# recorder.net
KiCad netlist of a schematic drawn in EAGLE
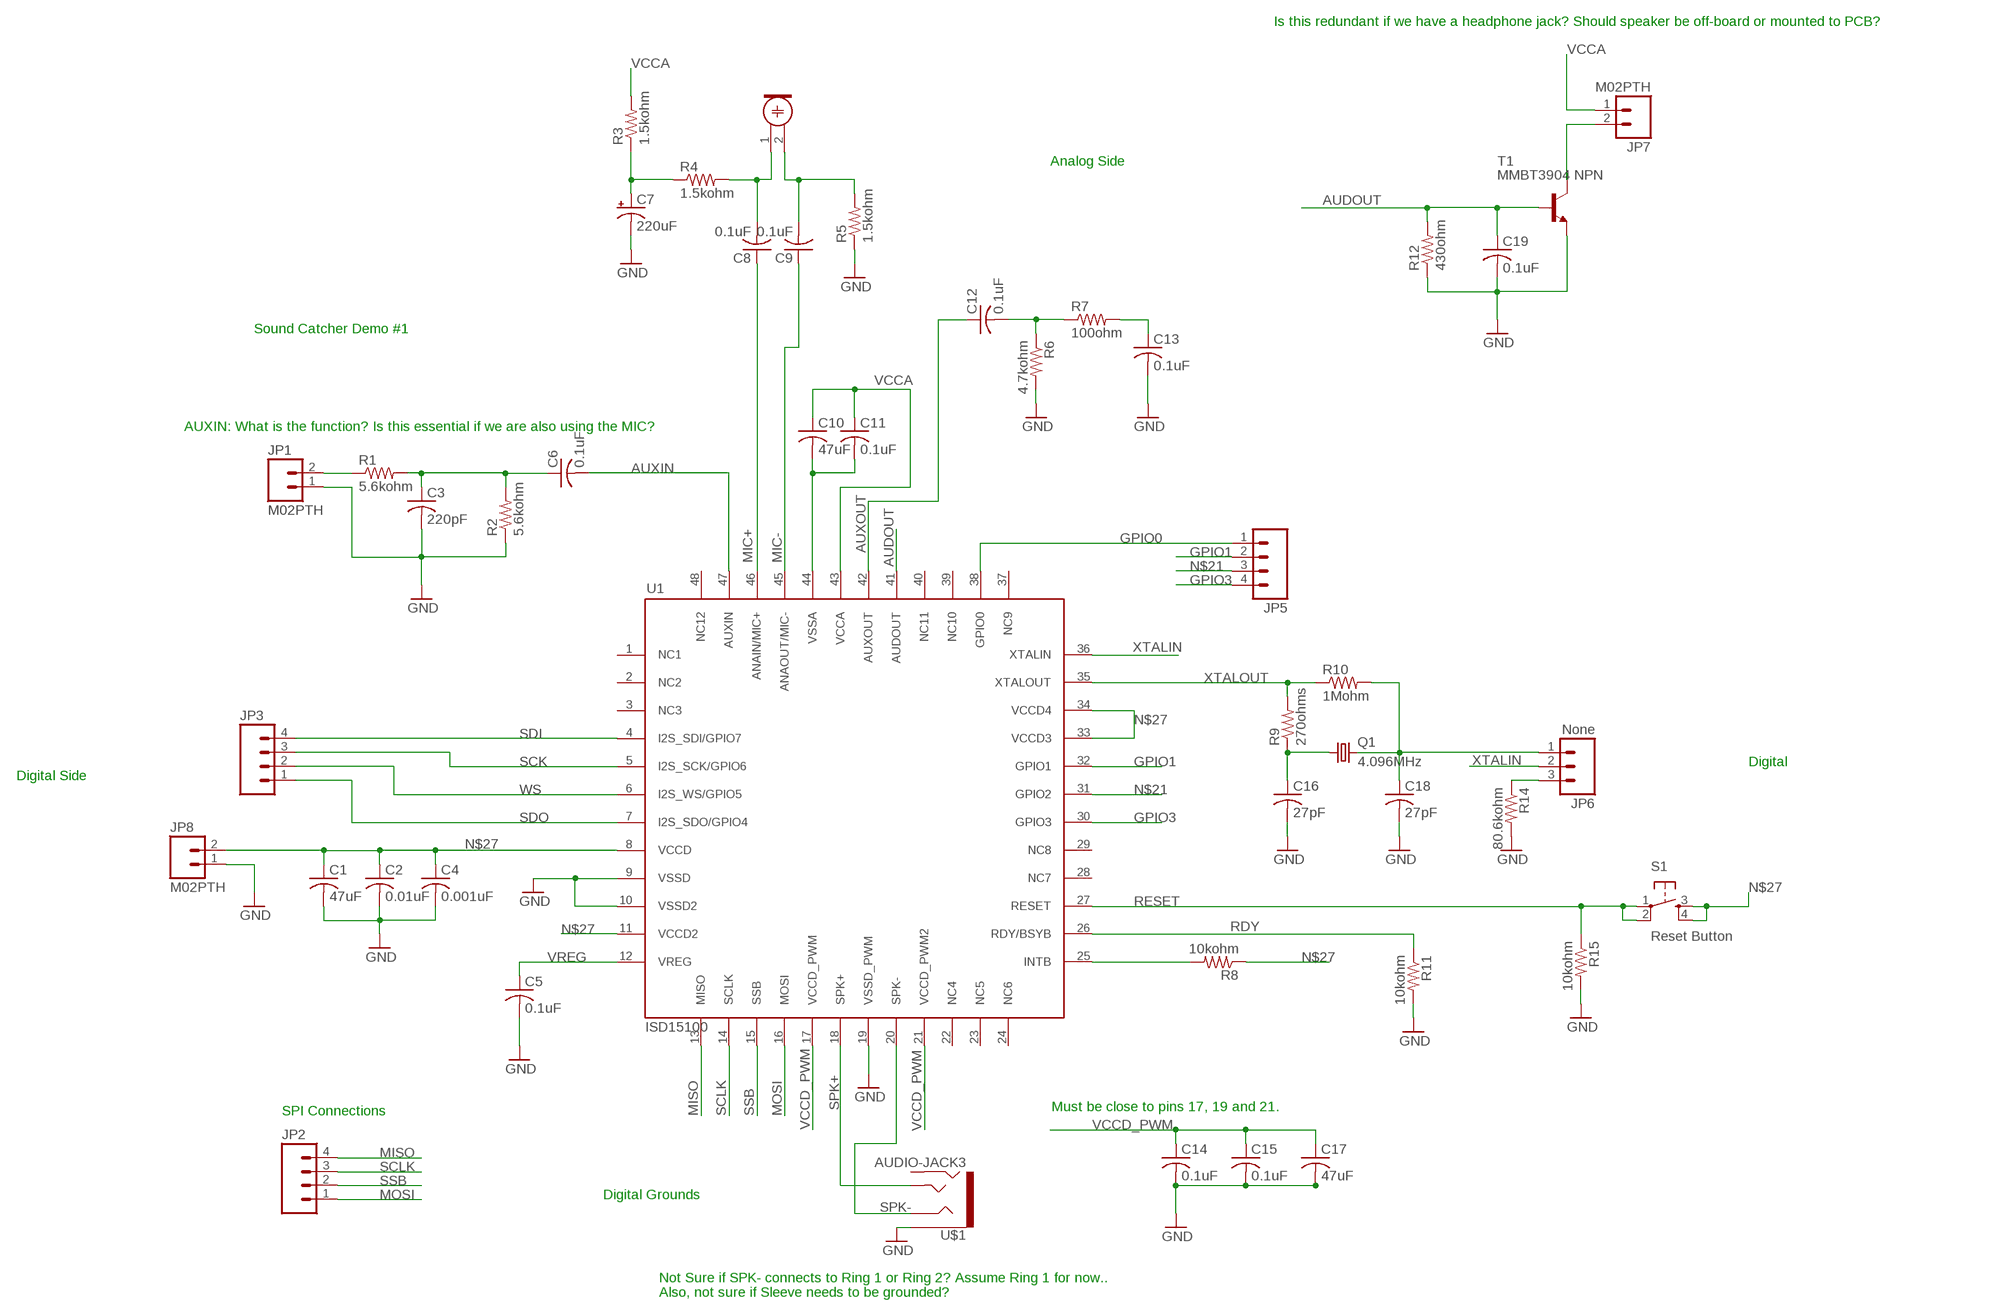
[diagram p0: schematic, sheet 1]

(export (version "E")
  (design (tool "Eeschema 10.0.6"))
  (components
    (comp (ref "C1")
      (value "47uF")
      (footprint "eagle-import:C1206")
      (libsource (lib "eagle-import") (part "C-USC1206"))
    )
    (comp (ref "C2")
      (value "0.01uF")
      (footprint "eagle-import:C0402")
      (libsource (lib "eagle-import") (part "C-USC0402"))
    )
    (comp (ref "C3")
      (value "220pF")
      (footprint "eagle-import:C0402")
      (libsource (lib "eagle-import") (part "C-USC0402"))
    )
    (comp (ref "C4")
      (value "0.001uF")
      (footprint "eagle-import:C0402")
      (libsource (lib "eagle-import") (part "C-USC0402"))
    )
    (comp (ref "C5")
      (value "0.1uF")
      (footprint "eagle-import:C0402")
      (libsource (lib "eagle-import") (part "C-USC0402"))
    )
    (comp (ref "C6")
      (value "0.1uF")
      (footprint "eagle-import:C0603")
      (libsource (lib "eagle-import") (part "C-USC0603"))
    )
    (comp (ref "C7")
      (value "220uF")
      (footprint "eagle-import:175TMP-0808")
      (libsource (lib "eagle-import") (part "CPOL-US175TMP-0808"))
    )
    (comp (ref "C8")
      (value "0.1uF")
      (footprint "eagle-import:C0402")
      (libsource (lib "eagle-import") (part "C-USC0402"))
    )
    (comp (ref "C9")
      (value "0.1uF")
      (footprint "eagle-import:C0402")
      (libsource (lib "eagle-import") (part "C-USC0402"))
    )
    (comp (ref "C10")
      (value "47uF")
      (footprint "eagle-import:C1206")
      (libsource (lib "eagle-import") (part "C-USC1206"))
    )
    (comp (ref "C11")
      (value "0.1uF")
      (footprint "eagle-import:C0402")
      (libsource (lib "eagle-import") (part "C-USC0402"))
    )
    (comp (ref "C12")
      (value "0.1uF")
      (footprint "eagle-import:C0402")
      (libsource (lib "eagle-import") (part "C-USC0402"))
    )
    (comp (ref "C13")
      (value "0.1uF")
      (footprint "eagle-import:C0402")
      (libsource (lib "eagle-import") (part "C-USC0402"))
    )
    (comp (ref "C14")
      (value "0.1uF")
      (footprint "eagle-import:C0402")
      (libsource (lib "eagle-import") (part "C-USC0402"))
    )
    (comp (ref "C15")
      (value "0.1uF")
      (footprint "eagle-import:C0402")
      (libsource (lib "eagle-import") (part "C-USC0402"))
    )
    (comp (ref "C16")
      (value "27pF")
      (footprint "eagle-import:C0402")
      (libsource (lib "eagle-import") (part "C-USC0402"))
    )
    (comp (ref "C17")
      (value "47uF")
      (footprint "eagle-import:C1206")
      (libsource (lib "eagle-import") (part "C-USC1206"))
    )
    (comp (ref "C18")
      (value "27pF")
      (footprint "eagle-import:C0402")
      (libsource (lib "eagle-import") (part "C-USC0402"))
    )
    (comp (ref "C19")
      (value "0.1uF")
      (footprint "eagle-import:C0402")
      (libsource (lib "eagle-import") (part "C-USC0402"))
    )
    (comp (ref "JP1")
      (value "M02PTH")
      (footprint "eagle-import:1X02")
      (libsource (lib "eagle-import") (part "M02PTH"))
    )
    (comp (ref "JP2")
      (value "M04PTH")
      (footprint "eagle-import:1X04")
      (libsource (lib "eagle-import") (part "M04PTH"))
    )
    (comp (ref "JP3")
      (value "M04PTH")
      (footprint "eagle-import:1X04")
      (libsource (lib "eagle-import") (part "M04PTH"))
    )
    (comp (ref "JP5")
      (value "M04PTH")
      (footprint "eagle-import:1X04")
      (libsource (lib "eagle-import") (part "M04PTH"))
    )
    (comp (ref "JP6")
      (value "None")
      (footprint "eagle-import:1X03")
      (libsource (lib "eagle-import") (part "M03PTH"))
    )
    (comp (ref "JP7")
      (value "M02PTH")
      (footprint "eagle-import:1X02")
      (libsource (lib "eagle-import") (part "M02PTH"))
    )
    (comp (ref "JP8")
      (value "M02PTH")
      (footprint "eagle-import:1X02")
      (libsource (lib "eagle-import") (part "M02PTH"))
    )
    (comp (ref "M1")
      (value "ELECTRET_MICROPHON-WM-61A")
      (footprint "eagle-import:WM-61A")
      (libsource (lib "eagle-import") (part "ELECTRET_MICROPHON-WM-61A"))
    )
    (comp (ref "Q1")
      (value "4.096MHz")
      (footprint "eagle-import:SM49")
      (libsource (lib "eagle-import") (part "CRYSTALSM49"))
    )
    (comp (ref "R1")
      (value "5.6kohm")
      (footprint "eagle-import:R0402")
      (libsource (lib "eagle-import") (part "R-US_R0402"))
    )
    (comp (ref "R2")
      (value "5.6kohm")
      (footprint "eagle-import:R0402")
      (libsource (lib "eagle-import") (part "R-US_R0402"))
    )
    (comp (ref "R3")
      (value "1.5kohm")
      (footprint "eagle-import:R0201")
      (fields (field (name "MF") "AVX CORPORATION") (field (name "MPN") "0402ZD104KAT2A"))
      (libsource (lib "eagle-import") (part "R-US_R0201"))
    )
    (comp (ref "R4")
      (value "1.5kohm")
      (footprint "eagle-import:R0201")
      (fields (field (name "MF") "AVX CORPORATION") (field (name "MPN") "0402ZD104KAT2A"))
      (libsource (lib "eagle-import") (part "R-US_R0201"))
    )
    (comp (ref "R5")
      (value "1.5kohm")
      (footprint "eagle-import:R0201")
      (fields (field (name "MF") "AVX CORPORATION") (field (name "MPN") "0402ZD104KAT2A"))
      (libsource (lib "eagle-import") (part "R-US_R0201"))
    )
    (comp (ref "R6")
      (value "4.7kohm")
      (footprint "eagle-import:R0201")
      (fields (field (name "MF") "AVX CORPORATION") (field (name "MPN") "0402ZD104KAT2A"))
      (libsource (lib "eagle-import") (part "R-US_R0201"))
    )
    (comp (ref "R7")
      (value "100ohm")
      (footprint "eagle-import:R0201")
      (fields (field (name "MF") "AVX CORPORATION") (field (name "MPN") "0402ZD104KAT2A"))
      (libsource (lib "eagle-import") (part "R-US_R0201"))
    )
    (comp (ref "R8")
      (value "10kohm")
      (footprint "eagle-import:R0201")
      (fields (field (name "MF") "AVX CORPORATION") (field (name "MPN") "0402ZD104KAT2A"))
      (libsource (lib "eagle-import") (part "R-US_R0201"))
    )
    (comp (ref "R9")
      (value "270ohms")
      (footprint "eagle-import:R0201")
      (fields (field (name "MF") "AVX CORPORATION") (field (name "MPN") "0402ZD104KAT2A"))
      (libsource (lib "eagle-import") (part "R-US_R0201"))
    )
    (comp (ref "R10")
      (value "1Mohm")
      (footprint "eagle-import:R0201")
      (fields (field (name "MF") "AVX CORPORATION") (field (name "MPN") "0402ZD104KAT2A"))
      (libsource (lib "eagle-import") (part "R-US_R0201"))
    )
    (comp (ref "R11")
      (value "10kohm")
      (footprint "eagle-import:R0201")
      (fields (field (name "MF") "AVX CORPORATION") (field (name "MPN") "0402ZD104KAT2A"))
      (libsource (lib "eagle-import") (part "R-US_R0201"))
    )
    (comp (ref "R12")
      (value "430ohm")
      (footprint "eagle-import:R0402")
      (libsource (lib "eagle-import") (part "R-US_R0402"))
    )
    (comp (ref "R14")
      (value "80.6kohm")
      (footprint "eagle-import:R0402")
      (libsource (lib "eagle-import") (part "R-US_R0402"))
    )
    (comp (ref "R15")
      (value "10kohm")
      (footprint "eagle-import:R0201")
      (fields (field (name "MF") "AVX CORPORATION") (field (name "MPN") "0402ZD104KAT2A"))
      (libsource (lib "eagle-import") (part "R-US_R0201"))
    )
    (comp (ref "S1")
      (value "Reset Button")
      (footprint "eagle-import:TACTILE-SWITCH-SMD")
      (libsource (lib "eagle-import") (part "TAC_SWITCHSMD"))
    )
    (comp (ref "T1")
      (value "MMBT3904 NPN")
      (footprint "eagle-import:SOT23-BEC")
      (libsource (lib "eagle-import") (part "-NPN-SOT23-BECMMBT3904LT1"))
    )
    (comp (ref "U$1")
      (value "AUDIO-JACK3")
      (footprint "eagle-import:AUDIO-JACK-TRRS-SMD")
      (libsource (lib "eagle-import") (part "AUDIO-JACK3"))
    )
    (comp (ref "U1")
      (value "ISD15100")
      (footprint "eagle-import:LQFP48")
      (libsource (lib "eagle-import") (part "ISD15100"))
    )
  )
  (nets
    (net (code "1") (name "/AUDOUT") (class "Default")
      (node (ref "C19") (pin "1") (pinfunction "1_1") (pintype "passive"))
      (node (ref "R12") (pin "2") (pinfunction "2_2") (pintype "passive"))
      (node (ref "T1") (pin "B") (pinfunction "B_B") (pintype "passive"))
      (node (ref "U1") (pin "41") (pinfunction "AUDOUT_41") (pintype "bidirectional"))
    )
    (net (code "2") (name "/AUXIN") (class "Default")
      (node (ref "C6") (pin "2") (pinfunction "2_2") (pintype "passive"))
      (node (ref "U1") (pin "47") (pinfunction "AUXIN_47") (pintype "bidirectional"))
    )
    (net (code "3") (name "/AUXOUT") (class "Default")
      (node (ref "C12") (pin "1") (pinfunction "1_1") (pintype "passive"))
      (node (ref "U1") (pin "42") (pinfunction "AUXOUT_42") (pintype "bidirectional"))
    )
    (net (code "4") (name "/GPIO0") (class "Default")
      (node (ref "JP5") (pin "1") (pinfunction "1_1") (pintype "passive"))
      (node (ref "U1") (pin "38") (pinfunction "GPIO0_38") (pintype "bidirectional"))
    )
    (net (code "5") (name "/GPIO1") (class "Default")
      (node (ref "JP5") (pin "2") (pinfunction "2_2") (pintype "passive"))
      (node (ref "U1") (pin "32") (pinfunction "GPIO1_32") (pintype "bidirectional"))
    )
    (net (code "6") (name "/GPIO3") (class "Default")
      (node (ref "JP5") (pin "4") (pinfunction "4_4") (pintype "passive"))
      (node (ref "U1") (pin "30") (pinfunction "GPIO3_30") (pintype "bidirectional"))
    )
    (net (code "7") (name "/MIC+") (class "Default")
      (node (ref "C8") (pin "1") (pinfunction "1_1") (pintype "passive"))
      (node (ref "U1") (pin "46") (pinfunction "ANAIN/MIC+_46") (pintype "bidirectional"))
    )
    (net (code "8") (name "/MIC-") (class "Default")
      (node (ref "C9") (pin "1") (pinfunction "1_1") (pintype "passive"))
      (node (ref "U1") (pin "45") (pinfunction "ANAOUT/MIC-_45") (pintype "bidirectional"))
    )
    (net (code "9") (name "/MISO") (class "Default")
      (node (ref "JP2") (pin "4") (pinfunction "4_4") (pintype "passive"))
      (node (ref "U1") (pin "13") (pinfunction "MISO_13") (pintype "bidirectional"))
    )
    (net (code "10") (name "/MOSI") (class "Default")
      (node (ref "JP2") (pin "1") (pinfunction "1_1") (pintype "passive"))
      (node (ref "U1") (pin "16") (pinfunction "MOSI_16") (pintype "bidirectional"))
    )
    (net (code "11") (name "/N$21") (class "Default")
      (node (ref "JP5") (pin "3") (pinfunction "3_3") (pintype "passive"))
      (node (ref "U1") (pin "31") (pinfunction "GPIO2_31") (pintype "bidirectional"))
    )
    (net (code "12") (name "/N$27") (class "Default")
      (node (ref "C1") (pin "1") (pinfunction "1_1") (pintype "passive"))
      (node (ref "C2") (pin "1") (pinfunction "1_1") (pintype "passive"))
      (node (ref "C4") (pin "1") (pinfunction "1_1") (pintype "passive"))
      (node (ref "JP8") (pin "2") (pinfunction "2_2") (pintype "passive"))
      (node (ref "R8") (pin "1") (pinfunction "1_1") (pintype "passive"))
      (node (ref "S1") (pin "3") (pinfunction "3_3") (pintype "passive"))
      (node (ref "S1") (pin "4") (pinfunction "4_4") (pintype "passive"))
      (node (ref "U1") (pin "11") (pinfunction "VCCD2_11") (pintype "bidirectional"))
      (node (ref "U1") (pin "33") (pinfunction "VCCD3_33") (pintype "bidirectional"))
      (node (ref "U1") (pin "34") (pinfunction "VCCD4_34") (pintype "bidirectional"))
      (node (ref "U1") (pin "8") (pinfunction "VCCD_8") (pintype "bidirectional"))
    )
    (net (code "13") (name "/RDY") (class "Default")
      (node (ref "R11") (pin "1") (pinfunction "1_1") (pintype "passive"))
      (node (ref "U1") (pin "26") (pinfunction "RDY/BSYB_26") (pintype "bidirectional"))
    )
    (net (code "14") (name "/RESET") (class "Default")
      (node (ref "R15") (pin "1") (pinfunction "1_1") (pintype "passive"))
      (node (ref "S1") (pin "1") (pinfunction "1_1") (pintype "passive"))
      (node (ref "S1") (pin "2") (pinfunction "2_2") (pintype "passive"))
      (node (ref "U1") (pin "27") (pinfunction "RESET_27") (pintype "bidirectional"))
    )
    (net (code "15") (name "/SCK") (class "Default")
      (node (ref "JP3") (pin "3") (pinfunction "3_3") (pintype "passive"))
      (node (ref "U1") (pin "5") (pinfunction "I2S_SCK/GPIO6_5") (pintype "bidirectional"))
    )
    (net (code "16") (name "/SCLK") (class "Default")
      (node (ref "JP2") (pin "3") (pinfunction "3_3") (pintype "passive"))
      (node (ref "U1") (pin "14") (pinfunction "SCLK_14") (pintype "bidirectional"))
    )
    (net (code "17") (name "/SDI") (class "Default")
      (node (ref "JP3") (pin "4") (pinfunction "4_4") (pintype "passive"))
      (node (ref "U1") (pin "4") (pinfunction "I2S_SDI/GPIO7_4") (pintype "bidirectional"))
    )
    (net (code "18") (name "/SDO") (class "Default")
      (node (ref "JP3") (pin "1") (pinfunction "1_1") (pintype "passive"))
      (node (ref "U1") (pin "7") (pinfunction "I2S_SDO/GPIO4_7") (pintype "bidirectional"))
    )
    (net (code "19") (name "/SPK+") (class "Default")
      (node (ref "U$1") (pin "TIP") (pinfunction "TIP_TIP") (pintype "bidirectional"))
      (node (ref "U1") (pin "18") (pinfunction "SPK+_18") (pintype "bidirectional"))
    )
    (net (code "20") (name "/SPK-") (class "Default")
      (node (ref "U$1") (pin "RING1") (pinfunction "RING1_RING1") (pintype "bidirectional"))
      (node (ref "U1") (pin "20") (pinfunction "SPK-_20") (pintype "bidirectional"))
    )
    (net (code "21") (name "/SSB") (class "Default")
      (node (ref "JP2") (pin "2") (pinfunction "2_2") (pintype "passive"))
      (node (ref "U1") (pin "15") (pinfunction "SSB_15") (pintype "bidirectional"))
    )
    (net (code "22") (name "/VCCA") (class "Default")
      (node (ref "C10") (pin "1") (pinfunction "1_1") (pintype "passive"))
      (node (ref "C11") (pin "1") (pinfunction "1_1") (pintype "passive"))
      (node (ref "JP7") (pin "1") (pinfunction "1_1") (pintype "passive"))
      (node (ref "R3") (pin "2") (pinfunction "2_2") (pintype "passive"))
      (node (ref "U1") (pin "43") (pinfunction "VCCA_43") (pintype "bidirectional"))
    )
    (net (code "23") (name "/VCCD_PWM") (class "Default")
      (node (ref "C14") (pin "1") (pinfunction "1_1") (pintype "passive"))
      (node (ref "C15") (pin "1") (pinfunction "1_1") (pintype "passive"))
      (node (ref "C17") (pin "1") (pinfunction "1_1") (pintype "passive"))
      (node (ref "U1") (pin "17") (pinfunction "VCCD_PWM_17") (pintype "bidirectional"))
      (node (ref "U1") (pin "21") (pinfunction "VCCD_PWM2_21") (pintype "bidirectional"))
    )
    (net (code "24") (name "/VREG") (class "Default")
      (node (ref "C5") (pin "1") (pinfunction "1_1") (pintype "passive"))
      (node (ref "U1") (pin "12") (pinfunction "VREG_12") (pintype "bidirectional"))
    )
    (net (code "25") (name "/WS") (class "Default")
      (node (ref "JP3") (pin "2") (pinfunction "2_2") (pintype "passive"))
      (node (ref "U1") (pin "6") (pinfunction "I2S_WS/GPIO5_6") (pintype "bidirectional"))
    )
    (net (code "26") (name "/XTALIN") (class "Default")
      (node (ref "JP6") (pin "2") (pinfunction "2_2") (pintype "passive"))
      (node (ref "U1") (pin "36") (pinfunction "XTALIN_36") (pintype "bidirectional"))
    )
    (net (code "27") (name "/XTALOUT") (class "Default")
      (node (ref "R10") (pin "1") (pinfunction "1_1") (pintype "passive"))
      (node (ref "R9") (pin "2") (pinfunction "2_2") (pintype "passive"))
      (node (ref "U1") (pin "35") (pinfunction "XTALOUT_35") (pintype "bidirectional"))
    )
    (net (code "28") (name "GND") (class "Default")
      (node (ref "C1") (pin "2") (pinfunction "2_2") (pintype "passive"))
      (node (ref "C13") (pin "2") (pinfunction "2_2") (pintype "passive"))
      (node (ref "C14") (pin "2") (pinfunction "2_2") (pintype "passive"))
      (node (ref "C15") (pin "2") (pinfunction "2_2") (pintype "passive"))
      (node (ref "C16") (pin "2") (pinfunction "2_2") (pintype "passive"))
      (node (ref "C17") (pin "2") (pinfunction "2_2") (pintype "passive"))
      (node (ref "C18") (pin "2") (pinfunction "2_2") (pintype "passive"))
      (node (ref "C19") (pin "2") (pinfunction "2_2") (pintype "passive"))
      (node (ref "C2") (pin "2") (pinfunction "2_2") (pintype "passive"))
      (node (ref "C3") (pin "2") (pinfunction "2_2") (pintype "passive"))
      (node (ref "C4") (pin "2") (pinfunction "2_2") (pintype "passive"))
      (node (ref "C5") (pin "2") (pinfunction "2_2") (pintype "passive"))
      (node (ref "C7") (pin "-") (pinfunction "-_-") (pintype "passive"))
      (node (ref "JP1") (pin "1") (pinfunction "1_1") (pintype "passive"))
      (node (ref "JP8") (pin "1") (pinfunction "1_1") (pintype "passive"))
      (node (ref "R11") (pin "2") (pinfunction "2_2") (pintype "passive"))
      (node (ref "R12") (pin "1") (pinfunction "1_1") (pintype "passive"))
      (node (ref "R14") (pin "2") (pinfunction "2_2") (pintype "passive"))
      (node (ref "R15") (pin "2") (pinfunction "2_2") (pintype "passive"))
      (node (ref "R2") (pin "1") (pinfunction "1_1") (pintype "passive"))
      (node (ref "R5") (pin "1") (pinfunction "1_1") (pintype "passive"))
      (node (ref "R6") (pin "2") (pinfunction "2_2") (pintype "passive"))
      (node (ref "T1") (pin "E") (pinfunction "E_E") (pintype "passive"))
      (node (ref "U$1") (pin "EARTH") (pinfunction "EARTH_EARTH") (pintype "bidirectional"))
      (node (ref "U1") (pin "10") (pinfunction "VSSD2_10") (pintype "bidirectional"))
      (node (ref "U1") (pin "19") (pinfunction "VSSD_PWM_19") (pintype "bidirectional"))
      (node (ref "U1") (pin "9") (pinfunction "VSSD_9") (pintype "bidirectional"))
    )
    (net (code "29") (name "Net-(C3-Pad1)") (class "Default")
      (node (ref "C3") (pin "1") (pinfunction "1_1") (pintype "passive"))
      (node (ref "C6") (pin "1") (pinfunction "1_1") (pintype "passive"))
      (node (ref "R1") (pin "2") (pinfunction "2_2") (pintype "passive"))
      (node (ref "R2") (pin "2") (pinfunction "2_2") (pintype "passive"))
    )
    (net (code "30") (name "Net-(C7-Pad+)") (class "Default")
      (node (ref "C7") (pin "+") (pinfunction "+_+") (pintype "passive"))
      (node (ref "R3") (pin "1") (pinfunction "1_1") (pintype "passive"))
      (node (ref "R4") (pin "1") (pinfunction "1_1") (pintype "passive"))
    )
    (net (code "31") (name "Net-(C8-Pad2)") (class "Default")
      (node (ref "C8") (pin "2") (pinfunction "2_2") (pintype "passive"))
      (node (ref "M1") (pin "1") (pinfunction "1_1") (pintype "passive"))
      (node (ref "R4") (pin "2") (pinfunction "2_2") (pintype "passive"))
    )
    (net (code "32") (name "Net-(C9-Pad2)") (class "Default")
      (node (ref "C9") (pin "2") (pinfunction "2_2") (pintype "passive"))
      (node (ref "M1") (pin "2") (pinfunction "2_2") (pintype "passive"))
      (node (ref "R5") (pin "2") (pinfunction "2_2") (pintype "passive"))
    )
    (net (code "33") (name "Net-(C12-Pad2)") (class "Default")
      (node (ref "C12") (pin "2") (pinfunction "2_2") (pintype "passive"))
      (node (ref "R6") (pin "1") (pinfunction "1_1") (pintype "passive"))
      (node (ref "R7") (pin "1") (pinfunction "1_1") (pintype "passive"))
    )
    (net (code "34") (name "Net-(C13-Pad1)") (class "Default")
      (node (ref "C13") (pin "1") (pinfunction "1_1") (pintype "passive"))
      (node (ref "R7") (pin "2") (pinfunction "2_2") (pintype "passive"))
    )
    (net (code "35") (name "Net-(C16-Pad1)") (class "Default")
      (node (ref "C16") (pin "1") (pinfunction "1_1") (pintype "passive"))
      (node (ref "Q1") (pin "1") (pinfunction "1_1") (pintype "passive"))
      (node (ref "R9") (pin "1") (pinfunction "1_1") (pintype "passive"))
    )
    (net (code "36") (name "Net-(C18-Pad1)") (class "Default")
      (node (ref "C18") (pin "1") (pinfunction "1_1") (pintype "passive"))
      (node (ref "JP6") (pin "1") (pinfunction "1_1") (pintype "passive"))
      (node (ref "Q1") (pin "2") (pinfunction "2_2") (pintype "passive"))
      (node (ref "R10") (pin "2") (pinfunction "2_2") (pintype "passive"))
    )
    (net (code "37") (name "Net-(JP1-Pad2)") (class "Default")
      (node (ref "JP1") (pin "2") (pinfunction "2_2") (pintype "passive"))
      (node (ref "R1") (pin "1") (pinfunction "1_1") (pintype "passive"))
    )
    (net (code "38") (name "Net-(JP6-Pad3)") (class "Default")
      (node (ref "JP6") (pin "3") (pinfunction "3_3") (pintype "passive"))
      (node (ref "R14") (pin "1") (pinfunction "1_1") (pintype "passive"))
    )
    (net (code "39") (name "Net-(JP7-Pad2)") (class "Default")
      (node (ref "JP7") (pin "2") (pinfunction "2_2") (pintype "passive"))
      (node (ref "T1") (pin "C") (pinfunction "C_C") (pintype "passive"))
    )
    (net (code "40") (name "Net-(U1-INTB)") (class "Default")
      (node (ref "R8") (pin "2") (pinfunction "2_2") (pintype "passive"))
      (node (ref "U1") (pin "25") (pinfunction "INTB_25") (pintype "bidirectional"))
    )
    (net (code "41") (name "Net-(U1-VSSA)") (class "Default")
      (node (ref "C10") (pin "2") (pinfunction "2_2") (pintype "passive"))
      (node (ref "C11") (pin "2") (pinfunction "2_2") (pintype "passive"))
      (node (ref "U1") (pin "44") (pinfunction "VSSA_44") (pintype "bidirectional"))
    )
    (net (code "42") (name "unconnected-(U$1-PadRING2)") (class "Default")
      (node (ref "U$1") (pin "RING2") (pinfunction "RING2_RING2") (pintype "bidirectional"))
    )
    (net (code "43") (name "unconnected-(U1-NC1-Pad1)") (class "Default")
      (node (ref "U1") (pin "1") (pinfunction "NC1_1") (pintype "bidirectional"))
    )
    (net (code "44") (name "unconnected-(U1-NC2-Pad2)") (class "Default")
      (node (ref "U1") (pin "2") (pinfunction "NC2_2") (pintype "bidirectional"))
    )
    (net (code "45") (name "unconnected-(U1-NC3-Pad3)") (class "Default")
      (node (ref "U1") (pin "3") (pinfunction "NC3_3") (pintype "bidirectional"))
    )
    (net (code "46") (name "unconnected-(U1-NC4-Pad22)") (class "Default")
      (node (ref "U1") (pin "22") (pinfunction "NC4_22") (pintype "bidirectional"))
    )
    (net (code "47") (name "unconnected-(U1-NC5-Pad23)") (class "Default")
      (node (ref "U1") (pin "23") (pinfunction "NC5_23") (pintype "bidirectional"))
    )
    (net (code "48") (name "unconnected-(U1-NC6-Pad24)") (class "Default")
      (node (ref "U1") (pin "24") (pinfunction "NC6_24") (pintype "bidirectional"))
    )
    (net (code "49") (name "unconnected-(U1-NC7-Pad28)") (class "Default")
      (node (ref "U1") (pin "28") (pinfunction "NC7_28") (pintype "bidirectional"))
    )
    (net (code "50") (name "unconnected-(U1-NC8-Pad29)") (class "Default")
      (node (ref "U1") (pin "29") (pinfunction "NC8_29") (pintype "bidirectional"))
    )
    (net (code "51") (name "unconnected-(U1-NC9-Pad37)") (class "Default")
      (node (ref "U1") (pin "37") (pinfunction "NC9_37") (pintype "bidirectional"))
    )
    (net (code "52") (name "unconnected-(U1-NC10-Pad39)") (class "Default")
      (node (ref "U1") (pin "39") (pinfunction "NC10_39") (pintype "bidirectional"))
    )
    (net (code "53") (name "unconnected-(U1-NC11-Pad40)") (class "Default")
      (node (ref "U1") (pin "40") (pinfunction "NC11_40") (pintype "bidirectional"))
    )
    (net (code "54") (name "unconnected-(U1-NC12-Pad48)") (class "Default")
      (node (ref "U1") (pin "48") (pinfunction "NC12_48") (pintype "bidirectional"))
    )
  )
)
